# sacredHeart.net
KiCad netlist of a schematic drawn in EAGLE
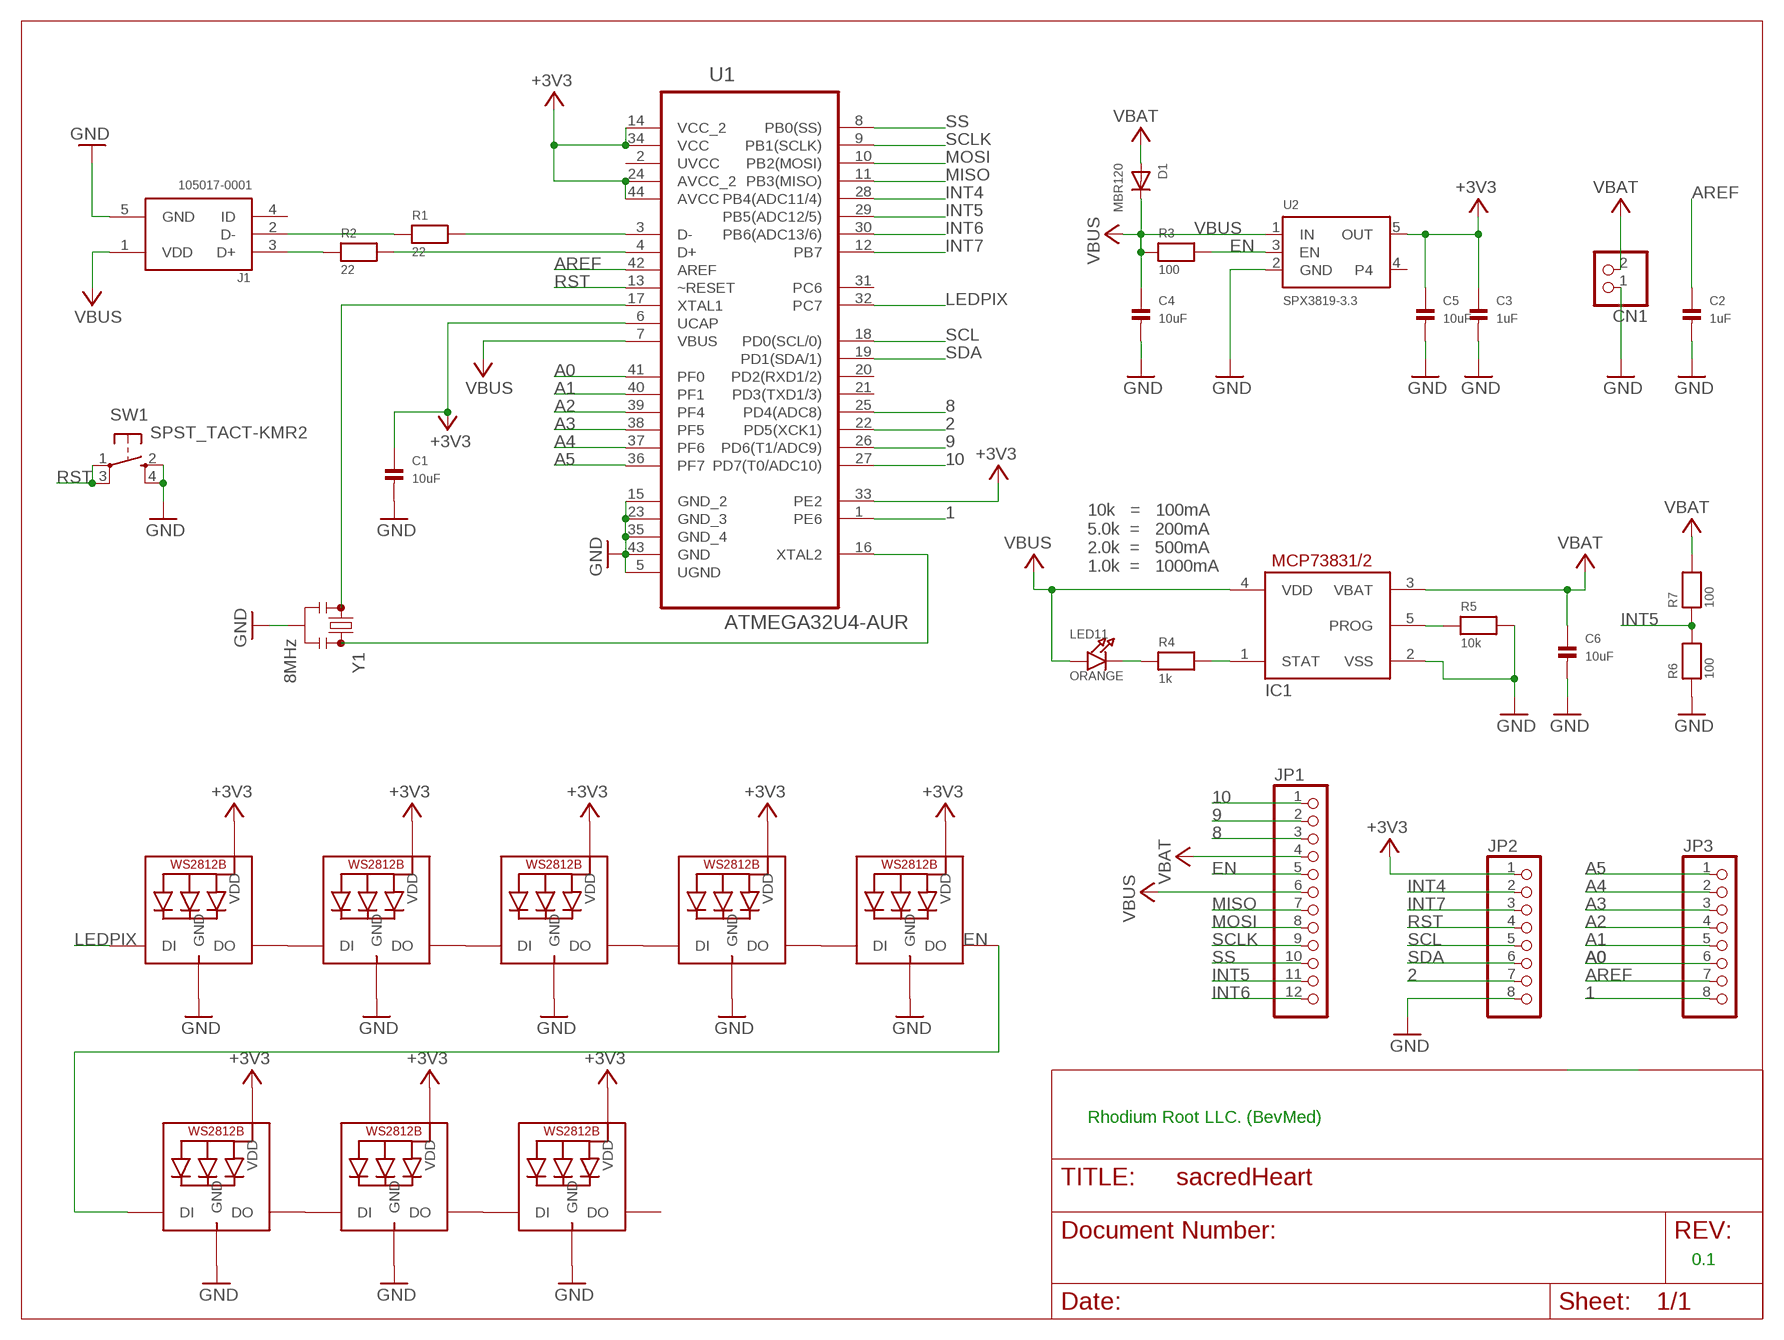
[diagram p0: schematic, sheet 1]

(export (version "E")
  (design (tool "Eeschema 10.0.6"))
  (components
    (comp (ref "C1")
      (value "10uF")
      (footprint "eagle-import:0805")
      (libsource (lib "eagle-import") (part "CAP_CERAMIC0805"))
    )
    (comp (ref "C2")
      (value "1uF")
      (footprint "eagle-import:0805")
      (fields (field (name "SPICEPREFIX") "C"))
      (libsource (lib "eagle-import") (part "CAP_CERAMIC0805"))
    )
    (comp (ref "C3")
      (value "1uF")
      (footprint "eagle-import:0805")
      (libsource (lib "eagle-import") (part "CAP_CERAMIC0805"))
    )
    (comp (ref "C4")
      (value "10uF")
      (footprint "eagle-import:0805")
      (libsource (lib "eagle-import") (part "CAP_CERAMIC0805"))
    )
    (comp (ref "C5")
      (value "10uF")
      (footprint "eagle-import:0805")
      (libsource (lib "eagle-import") (part "CAP_CERAMIC0805"))
    )
    (comp (ref "C6")
      (value "10uF")
      (footprint "eagle-import:0805")
      (fields (field (name "SPICEPREFIX") "C"))
      (libsource (lib "eagle-import") (part "CAP_CERAMIC0805"))
    )
    (comp (ref "CN1")
      (value "JST_2PIN")
      (footprint "eagle-import:JSTPH2")
      (libsource (lib "eagle-import") (part "JST_2PIN"))
    )
    (comp (ref "D1")
      (value "MBR120")
      (footprint "eagle-import:SOD-123")
      (libsource (lib "eagle-import") (part "DIODESOD-123"))
    )
    (comp (ref "IC1")
      (value "MCP73831/OT")
      (footprint "eagle-import:SOT23-5L")
      (libsource (lib "eagle-import") (part "MCP73831/OT"))
    )
    (comp (ref "J1")
      (value "105017-0001")
      (footprint "eagle-import:MOLEX_105017-0001")
      (fields (field (name "MF") "Molex"))
      (libsource (lib "eagle-import") (part "105017-0001"))
    )
    (comp (ref "JP1")
      (value "HEADER-1X12")
      (footprint "eagle-import:1X12_ROUND")
      (libsource (lib "eagle-import") (part "HEADER-1X12"))
    )
    (comp (ref "JP2")
      (value "HEADER-1X8ROUND")
      (footprint "eagle-import:1X08_ROUND")
      (libsource (lib "eagle-import") (part "HEADER-1X8ROUND"))
    )
    (comp (ref "JP3")
      (value "HEADER-1X8ROUND")
      (footprint "eagle-import:1X08_ROUND")
      (libsource (lib "eagle-import") (part "HEADER-1X8ROUND"))
    )
    (comp (ref "LED1")
      (value "WS2812B3535")
      (footprint "eagle-import:LED3535")
      (libsource (lib "eagle-import") (part "WS2812B3535"))
    )
    (comp (ref "LED2")
      (value "WS2812B3535")
      (footprint "eagle-import:LED3535")
      (libsource (lib "eagle-import") (part "WS2812B3535"))
    )
    (comp (ref "LED3")
      (value "WS2812B3535")
      (footprint "eagle-import:LED3535")
      (libsource (lib "eagle-import") (part "WS2812B3535"))
    )
    (comp (ref "LED4")
      (value "WS2812B3535")
      (footprint "eagle-import:LED3535")
      (libsource (lib "eagle-import") (part "WS2812B3535"))
    )
    (comp (ref "LED5")
      (value "WS2812B3535")
      (footprint "eagle-import:LED3535")
      (libsource (lib "eagle-import") (part "WS2812B3535"))
    )
    (comp (ref "LED6")
      (value "WS2812B3535")
      (footprint "eagle-import:LED3535")
      (libsource (lib "eagle-import") (part "WS2812B3535"))
    )
    (comp (ref "LED7")
      (value "WS2812B3535")
      (footprint "eagle-import:LED3535")
      (libsource (lib "eagle-import") (part "WS2812B3535"))
    )
    (comp (ref "LED8")
      (value "WS2812B3535")
      (footprint "eagle-import:LED3535")
      (libsource (lib "eagle-import") (part "WS2812B3535"))
    )
    (comp (ref "LED11")
      (value "ORANGE")
      (footprint "eagle-import:CHIPLED_0805_NOOUTLINE")
      (libsource (lib "eagle-import") (part "LED0805_NOOUTLINE"))
    )
    (comp (ref "R1")
      (value "22")
      (footprint "eagle-import:0603")
      (libsource (lib "eagle-import") (part "RESISTOR0603"))
    )
    (comp (ref "R2")
      (value "22")
      (footprint "eagle-import:0603")
      (libsource (lib "eagle-import") (part "RESISTOR0603"))
    )
    (comp (ref "R3")
      (value "100")
      (footprint "eagle-import:0603")
      (libsource (lib "eagle-import") (part "RESISTOR0603"))
    )
    (comp (ref "R4")
      (value "1k")
      (footprint "eagle-import:0603")
      (libsource (lib "eagle-import") (part "RESISTOR0603"))
    )
    (comp (ref "R5")
      (value "10k")
      (footprint "eagle-import:0603")
      (libsource (lib "eagle-import") (part "RESISTOR0603"))
    )
    (comp (ref "R6")
      (value "100")
      (footprint "eagle-import:0603")
      (libsource (lib "eagle-import") (part "RESISTOR0603"))
    )
    (comp (ref "R7")
      (value "100")
      (footprint "eagle-import:0603")
      (libsource (lib "eagle-import") (part "RESISTOR0603"))
    )
    (comp (ref "SW1")
      (value "SPST_TACT-KMR2")
      (footprint "eagle-import:KMR2")
      (libsource (lib "eagle-import") (part "SPST_TACT-KMR2"))
    )
    (comp (ref "U1")
      (value "ATMEGA32U4-AUR")
      (footprint "eagle-import:QFP80P1200X1200X120-44N")
      (fields (field (name "MF") "Microchip"))
      (libsource (lib "eagle-import") (part "ATMEGA32U4-AUR"))
    )
    (comp (ref "U2")
      (value "SPX3819-3.3")
      (footprint "eagle-import:SOT23-5")
      (libsource (lib "eagle-import") (part "VREG_SOT23-5"))
    )
    (comp (ref "Y1")
      (value "8MHz")
      (footprint "eagle-import:RESONATOR-SMD-3.2X1.3")
      (libsource (lib "eagle-import") (part "RESONATOR-8MHZSMD_3.2X1.3"))
    )
  )
  (nets
    (net (code "1") (name "+3V3") (class "Default")
      (node (ref "C1") (pin "1") (pinfunction "P$1_1") (pintype "passive"))
      (node (ref "C3") (pin "1") (pinfunction "P$1_1") (pintype "passive"))
      (node (ref "C5") (pin "1") (pinfunction "P$1_1") (pintype "passive"))
      (node (ref "JP2") (pin "1") (pinfunction "1_1") (pintype "passive"))
      (node (ref "LED1") (pin "2") (pinfunction "VDD_2") (pintype "power_in"))
      (node (ref "LED2") (pin "2") (pinfunction "VDD_2") (pintype "power_in"))
      (node (ref "LED3") (pin "2") (pinfunction "VDD_2") (pintype "power_in"))
      (node (ref "LED4") (pin "2") (pinfunction "VDD_2") (pintype "power_in"))
      (node (ref "LED5") (pin "2") (pinfunction "VDD_2") (pintype "power_in"))
      (node (ref "LED6") (pin "2") (pinfunction "VDD_2") (pintype "power_in"))
      (node (ref "LED7") (pin "2") (pinfunction "VDD_2") (pintype "power_in"))
      (node (ref "LED8") (pin "2") (pinfunction "VDD_2") (pintype "power_in"))
      (node (ref "U1") (pin "14") (pinfunction "VCC_2_14") (pintype "power_in"))
      (node (ref "U1") (pin "24") (pinfunction "AVCC_2_24") (pintype "power_in"))
      (node (ref "U1") (pin "33") (pinfunction "PE2_33") (pintype "bidirectional"))
      (node (ref "U1") (pin "34") (pinfunction "VCC_34") (pintype "power_in"))
      (node (ref "U1") (pin "44") (pinfunction "AVCC_44") (pintype "power_in"))
      (node (ref "U1") (pin "6") (pinfunction "UCAP_6") (pintype "power_in"))
      (node (ref "U2") (pin "5") (pinfunction "OUT_5") (pintype "bidirectional"))
    )
    (net (code "2") (name "/1") (class "Default")
      (node (ref "JP3") (pin "8") (pinfunction "8_8") (pintype "passive"))
      (node (ref "U1") (pin "1") (pinfunction "PE6_1") (pintype "bidirectional"))
    )
    (net (code "3") (name "/2") (class "Default")
      (node (ref "JP2") (pin "7") (pinfunction "7_7") (pintype "passive"))
      (node (ref "U1") (pin "22") (pinfunction "PD5(XCK1)_22") (pintype "bidirectional"))
    )
    (net (code "4") (name "/8") (class "Default")
      (node (ref "JP1") (pin "3") (pinfunction "3_3") (pintype "passive"))
      (node (ref "U1") (pin "25") (pinfunction "PD4(ADC8)_25") (pintype "bidirectional"))
    )
    (net (code "5") (name "/9") (class "Default")
      (node (ref "JP1") (pin "2") (pinfunction "2_2") (pintype "passive"))
      (node (ref "U1") (pin "26") (pinfunction "PD6(T1/ADC9)_26") (pintype "bidirectional"))
    )
    (net (code "6") (name "/10") (class "Default")
      (node (ref "JP1") (pin "1") (pinfunction "1_1") (pintype "passive"))
      (node (ref "U1") (pin "27") (pinfunction "PD7(T0/ADC10)_27") (pintype "bidirectional"))
    )
    (net (code "7") (name "/A0") (class "Default")
      (node (ref "JP3") (pin "6") (pinfunction "6_6") (pintype "passive"))
      (node (ref "U1") (pin "41") (pinfunction "PF0_41") (pintype "bidirectional"))
    )
    (net (code "8") (name "/A1") (class "Default")
      (node (ref "JP3") (pin "5") (pinfunction "5_5") (pintype "passive"))
      (node (ref "U1") (pin "40") (pinfunction "PF1_40") (pintype "bidirectional"))
    )
    (net (code "9") (name "/A2") (class "Default")
      (node (ref "JP3") (pin "4") (pinfunction "4_4") (pintype "passive"))
      (node (ref "U1") (pin "39") (pinfunction "PF4_39") (pintype "bidirectional"))
    )
    (net (code "10") (name "/A3") (class "Default")
      (node (ref "JP3") (pin "3") (pinfunction "3_3") (pintype "passive"))
      (node (ref "U1") (pin "38") (pinfunction "PF5_38") (pintype "bidirectional"))
    )
    (net (code "11") (name "/A4") (class "Default")
      (node (ref "JP3") (pin "2") (pinfunction "2_2") (pintype "passive"))
      (node (ref "U1") (pin "37") (pinfunction "PF6_37") (pintype "bidirectional"))
    )
    (net (code "12") (name "/A5") (class "Default")
      (node (ref "JP3") (pin "1") (pinfunction "1_1") (pintype "passive"))
      (node (ref "U1") (pin "36") (pinfunction "PF7_36") (pintype "bidirectional"))
    )
    (net (code "13") (name "/AREF") (class "Default")
      (node (ref "C2") (pin "1") (pinfunction "P$1_1") (pintype "passive"))
      (node (ref "JP3") (pin "7") (pinfunction "7_7") (pintype "passive"))
      (node (ref "U1") (pin "42") (pinfunction "AREF_42") (pintype "input"))
    )
    (net (code "14") (name "/EN") (class "Default")
      (node (ref "JP1") (pin "5") (pinfunction "5_5") (pintype "passive"))
      (node (ref "R3") (pin "2") (pinfunction "2_2") (pintype "passive"))
      (node (ref "U2") (pin "3") (pinfunction "EN_3") (pintype "bidirectional"))
    )
    (net (code "15") (name "/INT4") (class "Default")
      (node (ref "JP2") (pin "2") (pinfunction "2_2") (pintype "passive"))
      (node (ref "U1") (pin "28") (pinfunction "PB4(ADC11/4)_28") (pintype "bidirectional"))
    )
    (net (code "16") (name "/INT5") (class "Default")
      (node (ref "JP1") (pin "11") (pinfunction "11_11") (pintype "passive"))
      (node (ref "R6") (pin "2") (pinfunction "2_2") (pintype "passive"))
      (node (ref "R7") (pin "1") (pinfunction "1_1") (pintype "passive"))
      (node (ref "U1") (pin "29") (pinfunction "PB5(ADC12/5)_29") (pintype "bidirectional"))
    )
    (net (code "17") (name "/INT6") (class "Default")
      (node (ref "JP1") (pin "12") (pinfunction "12_12") (pintype "passive"))
      (node (ref "U1") (pin "30") (pinfunction "PB6(ADC13/6)_30") (pintype "bidirectional"))
    )
    (net (code "18") (name "/INT7") (class "Default")
      (node (ref "JP2") (pin "3") (pinfunction "3_3") (pintype "passive"))
      (node (ref "U1") (pin "12") (pinfunction "PB7_12") (pintype "bidirectional"))
    )
    (net (code "19") (name "/LEDPIX") (class "Default")
      (node (ref "LED1") (pin "1") (pinfunction "DI_1") (pintype "input"))
      (node (ref "U1") (pin "32") (pinfunction "PC7_32") (pintype "bidirectional"))
    )
    (net (code "20") (name "/MISO") (class "Default")
      (node (ref "JP1") (pin "7") (pinfunction "7_7") (pintype "passive"))
      (node (ref "U1") (pin "11") (pinfunction "PB3(MISO)_11") (pintype "bidirectional"))
    )
    (net (code "21") (name "/MOSI") (class "Default")
      (node (ref "JP1") (pin "8") (pinfunction "8_8") (pintype "passive"))
      (node (ref "U1") (pin "10") (pinfunction "PB2(MOSI)_10") (pintype "bidirectional"))
    )
    (net (code "22") (name "/RST") (class "Default")
      (node (ref "JP2") (pin "4") (pinfunction "4_4") (pintype "passive"))
      (node (ref "SW1") (pin "1") (pinfunction "P_1") (pintype "passive"))
      (node (ref "SW1") (pin "3") (pinfunction "P1_3") (pintype "passive"))
      (node (ref "U1") (pin "13") (pinfunction "~{RESET}_13") (pintype "input"))
    )
    (net (code "23") (name "/SCL") (class "Default")
      (node (ref "JP2") (pin "5") (pinfunction "5_5") (pintype "passive"))
      (node (ref "U1") (pin "18") (pinfunction "PD0(SCL/0)_18") (pintype "bidirectional"))
    )
    (net (code "24") (name "/SCLK") (class "Default")
      (node (ref "JP1") (pin "9") (pinfunction "9_9") (pintype "passive"))
      (node (ref "U1") (pin "9") (pinfunction "PB1(SCLK)_9") (pintype "bidirectional"))
    )
    (net (code "25") (name "/SDA") (class "Default")
      (node (ref "JP2") (pin "6") (pinfunction "6_6") (pintype "passive"))
      (node (ref "U1") (pin "19") (pinfunction "PD1(SDA/1)_19") (pintype "bidirectional"))
    )
    (net (code "26") (name "/SS") (class "Default")
      (node (ref "JP1") (pin "10") (pinfunction "10_10") (pintype "passive"))
      (node (ref "U1") (pin "8") (pinfunction "PB0(SS)_8") (pintype "bidirectional"))
    )
    (net (code "27") (name "/UVCC") (class "Default")
      (node (ref "U1") (pin "2") (pinfunction "UVCC_2") (pintype "power_in"))
    )
    (net (code "28") (name "GND") (class "Default")
      (node (ref "C1") (pin "2") (pinfunction "P$2_2") (pintype "passive"))
      (node (ref "C2") (pin "2") (pinfunction "P$2_2") (pintype "passive"))
      (node (ref "C3") (pin "2") (pinfunction "P$2_2") (pintype "passive"))
      (node (ref "C4") (pin "2") (pinfunction "P$2_2") (pintype "passive"))
      (node (ref "C5") (pin "2") (pinfunction "P$2_2") (pintype "passive"))
      (node (ref "C6") (pin "2") (pinfunction "P$2_2") (pintype "passive"))
      (node (ref "CN1") (pin "1") (pinfunction "1_1") (pintype "passive"))
      (node (ref "IC1") (pin "2") (pinfunction "VSS_2") (pintype "power_in"))
      (node (ref "J1") (pin "5") (pinfunction "GND_5") (pintype "power_in"))
      (node (ref "JP2") (pin "8") (pinfunction "8_8") (pintype "passive"))
      (node (ref "LED1") (pin "4") (pinfunction "GND_4") (pintype "power_in"))
      (node (ref "LED2") (pin "4") (pinfunction "GND_4") (pintype "power_in"))
      (node (ref "LED3") (pin "4") (pinfunction "GND_4") (pintype "power_in"))
      (node (ref "LED4") (pin "4") (pinfunction "GND_4") (pintype "power_in"))
      (node (ref "LED5") (pin "4") (pinfunction "GND_4") (pintype "power_in"))
      (node (ref "LED6") (pin "4") (pinfunction "GND_4") (pintype "power_in"))
      (node (ref "LED7") (pin "4") (pinfunction "GND_4") (pintype "power_in"))
      (node (ref "LED8") (pin "4") (pinfunction "GND_4") (pintype "power_in"))
      (node (ref "R5") (pin "2") (pinfunction "2_2") (pintype "passive"))
      (node (ref "R6") (pin "1") (pinfunction "1_1") (pintype "passive"))
      (node (ref "SW1") (pin "2") (pinfunction "S_2") (pintype "passive"))
      (node (ref "SW1") (pin "4") (pinfunction "S1_4") (pintype "passive"))
      (node (ref "U1") (pin "15") (pinfunction "GND_2_15") (pintype "passive"))
      (node (ref "U1") (pin "23") (pinfunction "GND_3_23") (pintype "passive"))
      (node (ref "U1") (pin "35") (pinfunction "GND_4_35") (pintype "passive"))
      (node (ref "U1") (pin "43") (pinfunction "GND_43") (pintype "passive"))
      (node (ref "U1") (pin "5") (pinfunction "UGND_5") (pintype "passive"))
      (node (ref "U2") (pin "2") (pinfunction "GND_2") (pintype "bidirectional"))
      (node (ref "Y1") (pin "2") (pinfunction "2_2") (pintype "passive"))
    )
    (net (code "29") (name "Net-(IC1-PROG)") (class "Default")
      (node (ref "IC1") (pin "5") (pinfunction "PROG_5") (pintype "input"))
      (node (ref "R5") (pin "1") (pinfunction "1_1") (pintype "passive"))
    )
    (net (code "30") (name "Net-(IC1-STAT)") (class "Default")
      (node (ref "IC1") (pin "1") (pinfunction "STAT_1") (pintype "output"))
      (node (ref "R4") (pin "2") (pinfunction "2_2") (pintype "passive"))
    )
    (net (code "31") (name "Net-(J1-D+)") (class "Default")
      (node (ref "J1") (pin "3") (pinfunction "D+_3") (pintype "bidirectional"))
      (node (ref "R2") (pin "1") (pinfunction "1_1") (pintype "passive"))
    )
    (net (code "32") (name "Net-(J1-D-)") (class "Default")
      (node (ref "J1") (pin "2") (pinfunction "D-_2") (pintype "bidirectional"))
      (node (ref "R1") (pin "1") (pinfunction "1_1") (pintype "passive"))
    )
    (net (code "33") (name "Net-(LED1-DO)") (class "Default")
      (node (ref "LED1") (pin "3") (pinfunction "DO_3") (pintype "output"))
      (node (ref "LED2") (pin "1") (pinfunction "DI_1") (pintype "input"))
    )
    (net (code "34") (name "Net-(LED2-DO)") (class "Default")
      (node (ref "LED2") (pin "3") (pinfunction "DO_3") (pintype "output"))
      (node (ref "LED3") (pin "1") (pinfunction "DI_1") (pintype "input"))
    )
    (net (code "35") (name "Net-(LED3-DO)") (class "Default")
      (node (ref "LED3") (pin "3") (pinfunction "DO_3") (pintype "output"))
      (node (ref "LED4") (pin "1") (pinfunction "DI_1") (pintype "input"))
    )
    (net (code "36") (name "Net-(LED4-DO)") (class "Default")
      (node (ref "LED4") (pin "3") (pinfunction "DO_3") (pintype "output"))
      (node (ref "LED5") (pin "1") (pinfunction "DI_1") (pintype "input"))
    )
    (net (code "37") (name "Net-(LED5-DO)") (class "Default")
      (node (ref "LED5") (pin "3") (pinfunction "DO_3") (pintype "output"))
      (node (ref "LED6") (pin "1") (pinfunction "DI_1") (pintype "input"))
    )
    (net (code "38") (name "Net-(LED6-DO)") (class "Default")
      (node (ref "LED6") (pin "3") (pinfunction "DO_3") (pintype "output"))
      (node (ref "LED7") (pin "1") (pinfunction "DI_1") (pintype "input"))
    )
    (net (code "39") (name "Net-(LED7-DO)") (class "Default")
      (node (ref "LED7") (pin "3") (pinfunction "DO_3") (pintype "output"))
      (node (ref "LED8") (pin "1") (pinfunction "DI_1") (pintype "input"))
    )
    (net (code "40") (name "Net-(LED11-PadC)") (class "Default")
      (node (ref "LED11") (pin "C") (pinfunction "C_C") (pintype "passive"))
      (node (ref "R4") (pin "1") (pinfunction "1_1") (pintype "passive"))
    )
    (net (code "41") (name "Net-(U1-D+)") (class "Default")
      (node (ref "R2") (pin "2") (pinfunction "2_2") (pintype "passive"))
      (node (ref "U1") (pin "4") (pinfunction "D+_4") (pintype "passive"))
    )
    (net (code "42") (name "Net-(U1-D-)") (class "Default")
      (node (ref "R1") (pin "2") (pinfunction "2_2") (pintype "passive"))
      (node (ref "U1") (pin "3") (pinfunction "D-_3") (pintype "passive"))
    )
    (net (code "43") (name "Net-(U1-XTAL1)") (class "Default")
      (node (ref "U1") (pin "17") (pinfunction "XTAL1_17") (pintype "input"))
      (node (ref "Y1") (pin "1") (pinfunction "1_1") (pintype "passive"))
    )
    (net (code "44") (name "Net-(U1-XTAL2)") (class "Default")
      (node (ref "U1") (pin "16") (pinfunction "XTAL2_16") (pintype "output"))
      (node (ref "Y1") (pin "3") (pinfunction "3_3") (pintype "passive"))
    )
    (net (code "45") (name "VBAT") (class "Default")
      (node (ref "C6") (pin "1") (pinfunction "P$1_1") (pintype "passive"))
      (node (ref "CN1") (pin "2") (pinfunction "2_2") (pintype "passive"))
      (node (ref "D1") (pin "A") (pinfunction "A_A") (pintype "passive"))
      (node (ref "IC1") (pin "3") (pinfunction "VBAT_3") (pintype "bidirectional"))
      (node (ref "JP1") (pin "4") (pinfunction "4_4") (pintype "passive"))
      (node (ref "R7") (pin "2") (pinfunction "2_2") (pintype "passive"))
    )
    (net (code "46") (name "VBUS") (class "Default")
      (node (ref "C4") (pin "1") (pinfunction "P$1_1") (pintype "passive"))
      (node (ref "D1") (pin "C") (pinfunction "C_C") (pintype "passive"))
      (node (ref "IC1") (pin "4") (pinfunction "VDD_4") (pintype "power_in"))
      (node (ref "J1") (pin "1") (pinfunction "VDD_1") (pintype "power_in"))
      (node (ref "JP1") (pin "6") (pinfunction "6_6") (pintype "passive"))
      (node (ref "LED11") (pin "A") (pinfunction "A_A") (pintype "passive"))
      (node (ref "R3") (pin "1") (pinfunction "1_1") (pintype "passive"))
      (node (ref "U1") (pin "7") (pinfunction "VBUS_7") (pintype "input"))
      (node (ref "U2") (pin "1") (pinfunction "IN_1") (pintype "bidirectional"))
    )
    (net (code "47") (name "unconnected-(J1-ID-Pad4)") (class "Default")
      (node (ref "J1") (pin "4") (pinfunction "ID_4") (pintype "passive"))
    )
    (net (code "48") (name "unconnected-(LED8-DO-Pad3)") (class "Default")
      (node (ref "LED8") (pin "3") (pinfunction "DO_3") (pintype "output"))
    )
    (net (code "49") (name "unconnected-(U1-PC6-Pad31)") (class "Default")
      (node (ref "U1") (pin "31") (pinfunction "PC6_31") (pintype "bidirectional"))
    )
    (net (code "50") (name "unconnected-(U1-PD2(RXD1{slash}2)-Pad20)") (class "Default")
      (node (ref "U1") (pin "20") (pinfunction "PD2(RXD1/2)_20") (pintype "bidirectional"))
    )
    (net (code "51") (name "unconnected-(U1-PD3(TXD1{slash}3)-Pad21)") (class "Default")
      (node (ref "U1") (pin "21") (pinfunction "PD3(TXD1/3)_21") (pintype "bidirectional"))
    )
    (net (code "52") (name "unconnected-(U2-P4-Pad4)") (class "Default")
      (node (ref "U2") (pin "4") (pinfunction "P4_4") (pintype "bidirectional"))
    )
  )
)
